# Papilio_DUO_2.net
KiCad netlist of a schematic drawn in Altium Designer
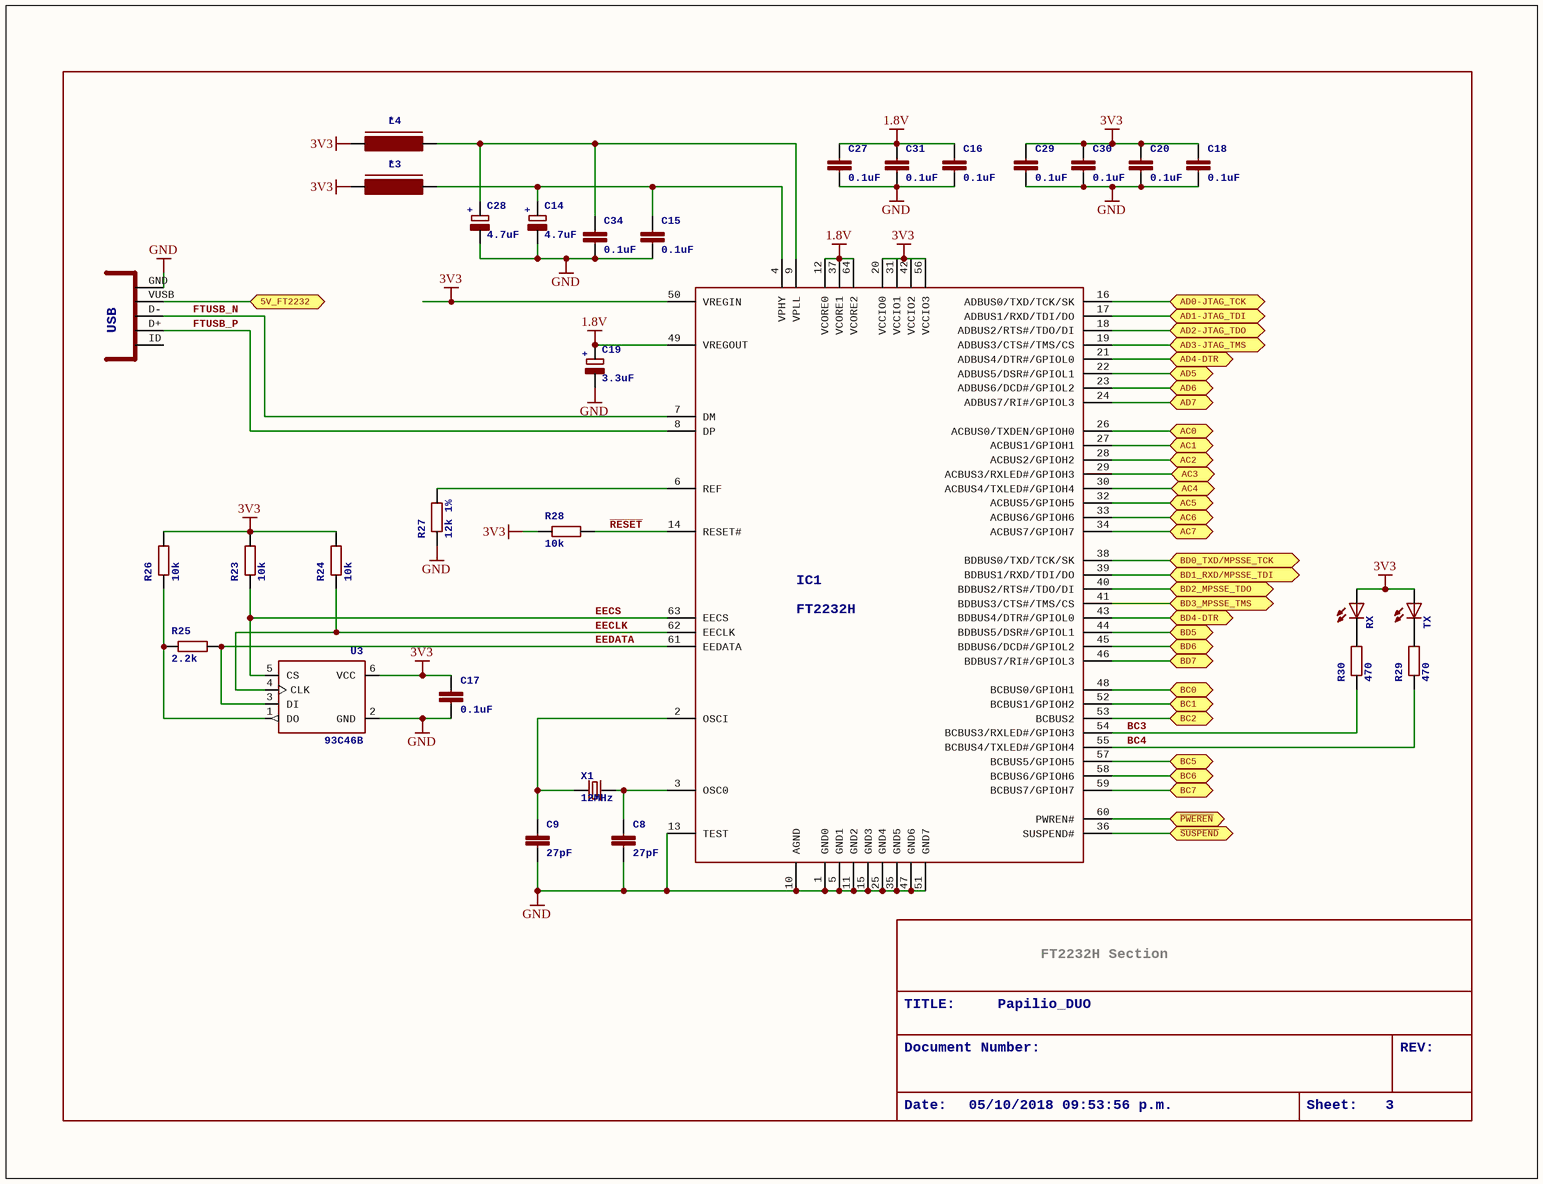
[diagram p0: Papilio_DUO_2.SchDoc]

(export (version "E")
  (design (tool "Eeschema 10.0.6"))
  (components
    (comp (ref "C8") (value "27pF") (footprint "C603") (libsource (lib "dp_devices") (part "CAPC603")))
    (comp (ref "C9") (value "27pF") (footprint "C603") (libsource (lib "dp_devices") (part "CAPC603")))
    (comp (ref "C14")
      (value "4.7uF")
      (footprint "SMC_A")
      (fields (field (name "+") "+"))
      (libsource (lib "dp_devices") (part "CAP_POLSMC_A"))
    )
    (comp (ref "C15") (value "0.1uF") (footprint "C603") (libsource (lib "dp_devices") (part "CAPC603")))
    (comp (ref "C16") (value "0.1uF") (footprint "C603") (libsource (lib "dp_devices") (part "CAPC603")))
    (comp (ref "C17") (value "0.1uF") (footprint "C603") (libsource (lib "dp_devices") (part "CAPC603")))
    (comp (ref "C18") (value "0.1uF") (footprint "C603") (libsource (lib "dp_devices") (part "CAPC603")))
    (comp (ref "C19")
      (value "3.3uF")
      (footprint "SMC_A")
      (fields (field (name "+") "+"))
      (libsource (lib "dp_devices") (part "CAP_POLSMC_A"))
    )
    (comp (ref "C20") (value "0.1uF") (footprint "C603") (libsource (lib "dp_devices") (part "CAPC603")))
    (comp (ref "C27") (value "0.1uF") (footprint "C603") (libsource (lib "dp_devices") (part "CAPC603")))
    (comp (ref "C28")
      (value "4.7uF")
      (footprint "SMC_A")
      (fields (field (name "+") "+"))
      (libsource (lib "dp_devices") (part "CAP_POLSMC_A"))
    )
    (comp (ref "C29") (value "0.1uF") (footprint "C603") (libsource (lib "dp_devices") (part "CAPC603")))
    (comp (ref "C30") (value "0.1uF") (footprint "C603") (libsource (lib "dp_devices") (part "CAPC603")))
    (comp (ref "C31") (value "0.1uF") (footprint "C603") (libsource (lib "dp_devices") (part "CAPC603")))
    (comp (ref "C34") (value "0.1uF") (footprint "C603") (libsource (lib "dp_devices") (part "CAPC603")))
    (comp (ref "FPGAUSB")
      (value "CONN_USB")
      (footprint "CONN_USB_MINI-B")
      (description "USB connector")
      (fields (field (name "USB") "USB"))
      (libsource (lib "dp_devices") (part "CONN_USB"))
    )
    (comp (ref "IC1")
      (value "FT2232H")
      (footprint "LQFP64")
      (description "DUAL HIGH SPEED USB TO MULTIPURPOSE UART/FIFO IC")
      (libsource (lib "DP-EagleLibrary") (part "FT2232H"))
    )
    (comp (ref "L3")
      (value "FERRITE_BEAD603")
      (footprint "FB603")
      (fields (field (name "NAME") "*"))
      (libsource (lib "dp_devices") (part "FERRITE_BEAD603"))
    )
    (comp (ref "L4")
      (value "FERRITE_BEAD603")
      (footprint "FB603")
      (fields (field (name "NAME") "*"))
      (libsource (lib "dp_devices") (part "FERRITE_BEAD603"))
    )
    (comp (ref "R23") (value "10k") (footprint "R603") (libsource (lib "dp_devices") (part "RESISTORR603")))
    (comp (ref "R24") (value "10k") (footprint "R603") (libsource (lib "dp_devices") (part "RESISTORR603")))
    (comp (ref "R25") (value "2.2k") (footprint "R603") (libsource (lib "dp_devices") (part "RESISTORR603")))
    (comp (ref "R26") (value "10k") (footprint "R603") (libsource (lib "dp_devices") (part "RESISTORR603")))
    (comp (ref "R27")
      (value "12k 1%")
      (footprint "R603")
      (libsource (lib "dp_devices") (part "RESISTORR603"))
    )
    (comp (ref "R28") (value "10k") (footprint "R603") (libsource (lib "dp_devices") (part "RESISTORR603")))
    (comp (ref "R29") (value "470") (footprint "R603") (libsource (lib "dp_devices") (part "RESISTORR603")))
    (comp (ref "R30") (value "470") (footprint "R603") (libsource (lib "dp_devices") (part "RESISTORR603")))
    (comp (ref "RX") (value "LED805") (footprint "LED-805") (libsource (lib "dp_devices") (part "LED805")))
    (comp (ref "TX") (value "LED805") (footprint "LED-805") (libsource (lib "dp_devices") (part "LED805")))
    (comp (ref "U3")
      (value "93C46B")
      (footprint "SOT23-6")
      (libsource (lib "Bogdan_Commons") (part "DIGITAL-EEPROM-MICROWIRE-6P_SOT23"))
    )
    (comp (ref "X1") (value "12MHz") (footprint "4X6") (libsource (lib "dp_devices") (part "CRYSTAL_212M_")))
  )
  (nets
    (net (code "1") (name "/5V_FT2232") (class "Default")
      (node (ref "FPGAUSB") (pin "VUSB") (pinfunction "VUSB_VUSB") (pintype "passive"))
    )
    (net (code "2") (name "/AC0") (class "Default")
      (node (ref "IC1") (pin "26") (pinfunction "ACBUS0/TXDEN/GPIOH0_26") (pintype "passive"))
    )
    (net (code "3") (name "/AC1") (class "Default")
      (node (ref "IC1") (pin "27") (pinfunction "ACBUS1/GPIOH1_27") (pintype "passive"))
    )
    (net (code "4") (name "/AC2") (class "Default")
      (node (ref "IC1") (pin "28") (pinfunction "ACBUS2/GPIOH2_28") (pintype "passive"))
    )
    (net (code "5") (name "/AC3") (class "Default")
      (node (ref "IC1") (pin "29") (pinfunction "ACBUS3/RXLED#/GPIOH3_29") (pintype "passive"))
    )
    (net (code "6") (name "/AC4") (class "Default")
      (node (ref "IC1") (pin "30") (pinfunction "ACBUS4/TXLED#/GPIOH4_30") (pintype "passive"))
    )
    (net (code "7") (name "/AC5") (class "Default")
      (node (ref "IC1") (pin "32") (pinfunction "ACBUS5/GPIOH5_32") (pintype "passive"))
    )
    (net (code "8") (name "/AC6") (class "Default")
      (node (ref "IC1") (pin "33") (pinfunction "ACBUS6/GPIOH6_33") (pintype "passive"))
    )
    (net (code "9") (name "/AC7") (class "Default")
      (node (ref "IC1") (pin "34") (pinfunction "ACBUS7/GPIOH7_34") (pintype "passive"))
    )
    (net (code "10") (name "/AD0-JTAG_TCK") (class "Default")
      (node (ref "IC1") (pin "16") (pinfunction "ADBUS0/TXD/TCK/SK_16") (pintype "passive"))
    )
    (net (code "11") (name "/AD1-JTAG_TDI") (class "Default")
      (node (ref "IC1") (pin "17") (pinfunction "ADBUS1/RXD/TDI/DO_17") (pintype "passive"))
    )
    (net (code "12") (name "/AD2-JTAG_TDO") (class "Default")
      (node (ref "IC1") (pin "18") (pinfunction "ADBUS2/RTS#/TDO/DI_18") (pintype "passive"))
    )
    (net (code "13") (name "/AD3-JTAG_TMS") (class "Default")
      (node (ref "IC1") (pin "19") (pinfunction "ADBUS3/CTS#/TMS/CS_19") (pintype "passive"))
    )
    (net (code "14") (name "/AD4-DTR") (class "Default")
      (node (ref "IC1") (pin "21") (pinfunction "ADBUS4/DTR#/GPIOL0_21") (pintype "passive"))
    )
    (net (code "15") (name "/AD5") (class "Default")
      (node (ref "IC1") (pin "22") (pinfunction "ADBUS5/DSR#/GPIOL1_22") (pintype "passive"))
    )
    (net (code "16") (name "/AD6") (class "Default")
      (node (ref "IC1") (pin "23") (pinfunction "ADBUS6/DCD#/GPIOL2_23") (pintype "passive"))
    )
    (net (code "17") (name "/AD7") (class "Default")
      (node (ref "IC1") (pin "24") (pinfunction "ADBUS7/RI#/GPIOL3_24") (pintype "passive"))
    )
    (net (code "18") (name "/BC0") (class "Default")
      (node (ref "IC1") (pin "48") (pinfunction "BCBUS0/GPIOH1_48") (pintype "passive"))
    )
    (net (code "19") (name "/BC1") (class "Default")
      (node (ref "IC1") (pin "52") (pinfunction "BCBUS1/GPIOH2_52") (pintype "passive"))
    )
    (net (code "20") (name "/BC2") (class "Default")
      (node (ref "IC1") (pin "53") (pinfunction "BCBUS2_53") (pintype "passive"))
    )
    (net (code "21") (name "/BC3") (class "Default")
      (node (ref "IC1") (pin "54") (pinfunction "BCBUS3/RXLED#/GPIOH3_54") (pintype "passive"))
      (node (ref "R30") (pin "1") (pinfunction "1_1") (pintype "passive"))
    )
    (net (code "22") (name "/BC4") (class "Default")
      (node (ref "IC1") (pin "55") (pinfunction "BCBUS4/TXLED#/GPIOH4_55") (pintype "passive"))
      (node (ref "R29") (pin "1") (pinfunction "1_1") (pintype "passive"))
    )
    (net (code "23") (name "/BC5") (class "Default")
      (node (ref "IC1") (pin "57") (pinfunction "BCBUS5/GPIOH5_57") (pintype "passive"))
    )
    (net (code "24") (name "/BC6") (class "Default")
      (node (ref "IC1") (pin "58") (pinfunction "BCBUS6/GPIOH6_58") (pintype "passive"))
    )
    (net (code "25") (name "/BC7") (class "Default")
      (node (ref "IC1") (pin "59") (pinfunction "BCBUS7/GPIOH7_59") (pintype "passive"))
    )
    (net (code "26") (name "/BD0_TXD{slash}MPSSE_TCK") (class "Default")
      (node (ref "IC1") (pin "38") (pinfunction "BDBUS0/TXD/TCK/SK_38") (pintype "passive"))
    )
    (net (code "27") (name "/BD1_RXD{slash}MPSSE_TDI") (class "Default")
      (node (ref "IC1") (pin "39") (pinfunction "BDBUS1/RXD/TDI/DO_39") (pintype "passive"))
    )
    (net (code "28") (name "/BD2_MPSSE_TDO") (class "Default")
      (node (ref "IC1") (pin "40") (pinfunction "BDBUS2/RTS#/TDO/DI_40") (pintype "passive"))
    )
    (net (code "29") (name "/BD3_MPSSE_TMS") (class "Default")
      (node (ref "IC1") (pin "41") (pinfunction "BDBUS3/CTS#/TMS/CS_41") (pintype "passive"))
    )
    (net (code "30") (name "/BD4-DTR") (class "Default")
      (node (ref "IC1") (pin "43") (pinfunction "BDBUS4/DTR#/GPIOL0_43") (pintype "passive"))
    )
    (net (code "31") (name "/BD5") (class "Default")
      (node (ref "IC1") (pin "44") (pinfunction "BDBUS5/DSR#/GPIOL1_44") (pintype "passive"))
    )
    (net (code "32") (name "/BD6") (class "Default")
      (node (ref "IC1") (pin "45") (pinfunction "BDBUS6/DCD#/GPIOL2_45") (pintype "passive"))
    )
    (net (code "33") (name "/BD7") (class "Default")
      (node (ref "IC1") (pin "46") (pinfunction "BDBUS7/RI#/GPIOL3_46") (pintype "passive"))
    )
    (net (code "34") (name "/EECLK") (class "Default")
      (node (ref "IC1") (pin "62") (pinfunction "EECLK_62") (pintype "passive"))
      (node (ref "R24") (pin "1") (pinfunction "1_1") (pintype "passive"))
      (node (ref "U3") (pin "4") (pinfunction "CLK_4") (pintype "passive"))
    )
    (net (code "35") (name "/EECS") (class "Default")
      (node (ref "IC1") (pin "63") (pinfunction "EECS_63") (pintype "passive"))
      (node (ref "R23") (pin "1") (pinfunction "1_1") (pintype "passive"))
      (node (ref "U3") (pin "5") (pinfunction "CS_5") (pintype "passive"))
    )
    (net (code "36") (name "/EEDATA") (class "Default")
      (node (ref "IC1") (pin "61") (pinfunction "EEDATA_61") (pintype "passive"))
      (node (ref "R25") (pin "2") (pinfunction "2_2") (pintype "passive"))
      (node (ref "U3") (pin "3") (pinfunction "DI_3") (pintype "passive"))
    )
    (net (code "37") (name "/FTUSB_N") (class "Default")
      (node (ref "FPGAUSB") (pin "D-") (pinfunction "D-_D-") (pintype "passive"))
      (node (ref "IC1") (pin "7") (pinfunction "DM_7") (pintype "passive"))
    )
    (net (code "38") (name "/FTUSB_P") (class "Default")
      (node (ref "FPGAUSB") (pin "D+") (pinfunction "D+_D+") (pintype "passive"))
      (node (ref "IC1") (pin "8") (pinfunction "DP_8") (pintype "passive"))
    )
    (net (code "39") (name "/~{PWEREN}") (class "Default")
      (node (ref "IC1") (pin "60") (pinfunction "PWREN#_60") (pintype "passive"))
    )
    (net (code "40") (name "/~{RESET}") (class "Default")
      (node (ref "IC1") (pin "14") (pinfunction "RESET#_14") (pintype "passive"))
      (node (ref "R28") (pin "2") (pinfunction "2_2") (pintype "passive"))
    )
    (net (code "41") (name "/~{SUSPEND}") (class "Default")
      (node (ref "IC1") (pin "36") (pinfunction "SUSPEND#_36") (pintype "passive"))
    )
    (net (code "42") (name "1.8V") (class "Default")
      (node (ref "C16") (pin "1") (pinfunction "1_1") (pintype "passive"))
      (node (ref "C19") (pin "+") (pinfunction "+_+") (pintype "passive"))
      (node (ref "C27") (pin "1") (pinfunction "1_1") (pintype "passive"))
      (node (ref "C31") (pin "1") (pinfunction "1_1") (pintype "passive"))
      (node (ref "IC1") (pin "12") (pinfunction "VCORE0_12") (pintype "passive"))
      (node (ref "IC1") (pin "37") (pinfunction "VCORE1_37") (pintype "passive"))
      (node (ref "IC1") (pin "49") (pinfunction "VREGOUT_49") (pintype "passive"))
      (node (ref "IC1") (pin "64") (pinfunction "VCORE2_64") (pintype "passive"))
    )
    (net (code "43") (name "3V3") (class "Default")
      (node (ref "C17") (pin "1") (pinfunction "1_1") (pintype "passive"))
      (node (ref "C18") (pin "1") (pinfunction "1_1") (pintype "passive"))
      (node (ref "C20") (pin "1") (pinfunction "1_1") (pintype "passive"))
      (node (ref "C29") (pin "1") (pinfunction "1_1") (pintype "passive"))
      (node (ref "C30") (pin "1") (pinfunction "1_1") (pintype "passive"))
      (node (ref "IC1") (pin "20") (pinfunction "VCCIO0_20") (pintype "passive"))
      (node (ref "IC1") (pin "31") (pinfunction "VCCIO1_31") (pintype "passive"))
      (node (ref "IC1") (pin "42") (pinfunction "VCCIO2_42") (pintype "passive"))
      (node (ref "IC1") (pin "50") (pinfunction "VREGIN_50") (pintype "passive"))
      (node (ref "IC1") (pin "56") (pinfunction "VCCIO3_56") (pintype "passive"))
      (node (ref "L3") (pin "2") (pinfunction "2_2") (pintype "passive"))
      (node (ref "L4") (pin "2") (pinfunction "2_2") (pintype "passive"))
      (node (ref "R23") (pin "2") (pinfunction "2_2") (pintype "passive"))
      (node (ref "R24") (pin "2") (pinfunction "2_2") (pintype "passive"))
      (node (ref "R26") (pin "2") (pinfunction "2_2") (pintype "passive"))
      (node (ref "R28") (pin "1") (pinfunction "1_1") (pintype "passive"))
      (node (ref "RX") (pin "A") (pinfunction "A_A") (pintype "passive"))
      (node (ref "TX") (pin "A") (pinfunction "A_A") (pintype "passive"))
      (node (ref "U3") (pin "6") (pinfunction "VCC_6") (pintype "passive"))
    )
    (net (code "44") (name "GND") (class "Default")
      (node (ref "C14") (pin "-") (pinfunction "-_-") (pintype "passive"))
      (node (ref "C15") (pin "2") (pinfunction "2_2") (pintype "passive"))
      (node (ref "C16") (pin "2") (pinfunction "2_2") (pintype "passive"))
      (node (ref "C17") (pin "2") (pinfunction "2_2") (pintype "passive"))
      (node (ref "C18") (pin "2") (pinfunction "2_2") (pintype "passive"))
      (node (ref "C19") (pin "-") (pinfunction "-_-") (pintype "passive"))
      (node (ref "C20") (pin "2") (pinfunction "2_2") (pintype "passive"))
      (node (ref "C27") (pin "2") (pinfunction "2_2") (pintype "passive"))
      (node (ref "C28") (pin "-") (pinfunction "-_-") (pintype "passive"))
      (node (ref "C29") (pin "2") (pinfunction "2_2") (pintype "passive"))
      (node (ref "C30") (pin "2") (pinfunction "2_2") (pintype "passive"))
      (node (ref "C31") (pin "2") (pinfunction "2_2") (pintype "passive"))
      (node (ref "C34") (pin "2") (pinfunction "2_2") (pintype "passive"))
      (node (ref "C8") (pin "2") (pinfunction "2_2") (pintype "passive"))
      (node (ref "C9") (pin "2") (pinfunction "2_2") (pintype "passive"))
      (node (ref "FPGAUSB") (pin "GND") (pinfunction "GND_GND") (pintype "passive"))
      (node (ref "IC1") (pin "1") (pinfunction "GND0_1") (pintype "passive"))
      (node (ref "IC1") (pin "10") (pinfunction "AGND_10") (pintype "passive"))
      (node (ref "IC1") (pin "11") (pinfunction "GND2_11") (pintype "passive"))
      (node (ref "IC1") (pin "13") (pinfunction "TEST_13") (pintype "passive"))
      (node (ref "IC1") (pin "15") (pinfunction "GND3_15") (pintype "passive"))
      (node (ref "IC1") (pin "25") (pinfunction "GND4_25") (pintype "passive"))
      (node (ref "IC1") (pin "35") (pinfunction "GND5_35") (pintype "passive"))
      (node (ref "IC1") (pin "47") (pinfunction "GND6_47") (pintype "passive"))
      (node (ref "IC1") (pin "5") (pinfunction "GND1_5") (pintype "passive"))
      (node (ref "IC1") (pin "51") (pinfunction "GND7_51") (pintype "passive"))
      (node (ref "R27") (pin "1") (pinfunction "1_1") (pintype "passive"))
      (node (ref "U3") (pin "2") (pinfunction "GND_2") (pintype "power_in"))
    )
    (net (code "45") (name "Net-(IC1-OSC0)") (class "Default")
      (node (ref "C8") (pin "1") (pinfunction "1_1") (pintype "passive"))
      (node (ref "IC1") (pin "3") (pinfunction "OSC0_3") (pintype "passive"))
      (node (ref "X1") (pin "2") (pinfunction "X2_2") (pintype "passive"))
    )
    (net (code "46") (name "Net-(IC1-OSCI)") (class "Default")
      (node (ref "C9") (pin "1") (pinfunction "1_1") (pintype "passive"))
      (node (ref "IC1") (pin "2") (pinfunction "OSCI_2") (pintype "passive"))
      (node (ref "X1") (pin "1") (pinfunction "X1_1") (pintype "passive"))
    )
    (net (code "47") (name "Net-(IC1-REF)") (class "Default")
      (node (ref "IC1") (pin "6") (pinfunction "REF_6") (pintype "passive"))
      (node (ref "R27") (pin "2") (pinfunction "2_2") (pintype "passive"))
    )
    (net (code "48") (name "Net-(IC1-VPHY)") (class "Default")
      (node (ref "C14") (pin "+") (pinfunction "+_+") (pintype "passive"))
      (node (ref "C15") (pin "1") (pinfunction "1_1") (pintype "passive"))
      (node (ref "IC1") (pin "4") (pinfunction "VPHY_4") (pintype "passive"))
      (node (ref "L3") (pin "1") (pinfunction "1_1") (pintype "passive"))
    )
    (net (code "49") (name "Net-(IC1-VPLL)") (class "Default")
      (node (ref "C28") (pin "+") (pinfunction "+_+") (pintype "passive"))
      (node (ref "C34") (pin "1") (pinfunction "1_1") (pintype "passive"))
      (node (ref "IC1") (pin "9") (pinfunction "VPLL_9") (pintype "passive"))
      (node (ref "L4") (pin "1") (pinfunction "1_1") (pintype "passive"))
    )
    (net (code "50") (name "Net-(R29-Pad2)") (class "Default")
      (node (ref "R29") (pin "2") (pinfunction "2_2") (pintype "passive"))
      (node (ref "TX") (pin "C") (pinfunction "C_C") (pintype "passive"))
    )
    (net (code "51") (name "Net-(R30-Pad2)") (class "Default")
      (node (ref "R30") (pin "2") (pinfunction "2_2") (pintype "passive"))
      (node (ref "RX") (pin "C") (pinfunction "C_C") (pintype "passive"))
    )
    (net (code "52") (name "Net-(U3-DO)") (class "Default")
      (node (ref "R25") (pin "1") (pinfunction "1_1") (pintype "passive"))
      (node (ref "R26") (pin "1") (pinfunction "1_1") (pintype "passive"))
      (node (ref "U3") (pin "1") (pinfunction "DO_1") (pintype "output"))
    )
    (net (code "53") (name "unconnected-(FPGAUSB-USBID-PadID)") (class "Default")
      (node (ref "FPGAUSB") (pin "ID") (pinfunction "USBID_ID") (pintype "passive"))
    )
  )
)
